# waterworx.net
KiCad netlist of a schematic drawn in EAGLE
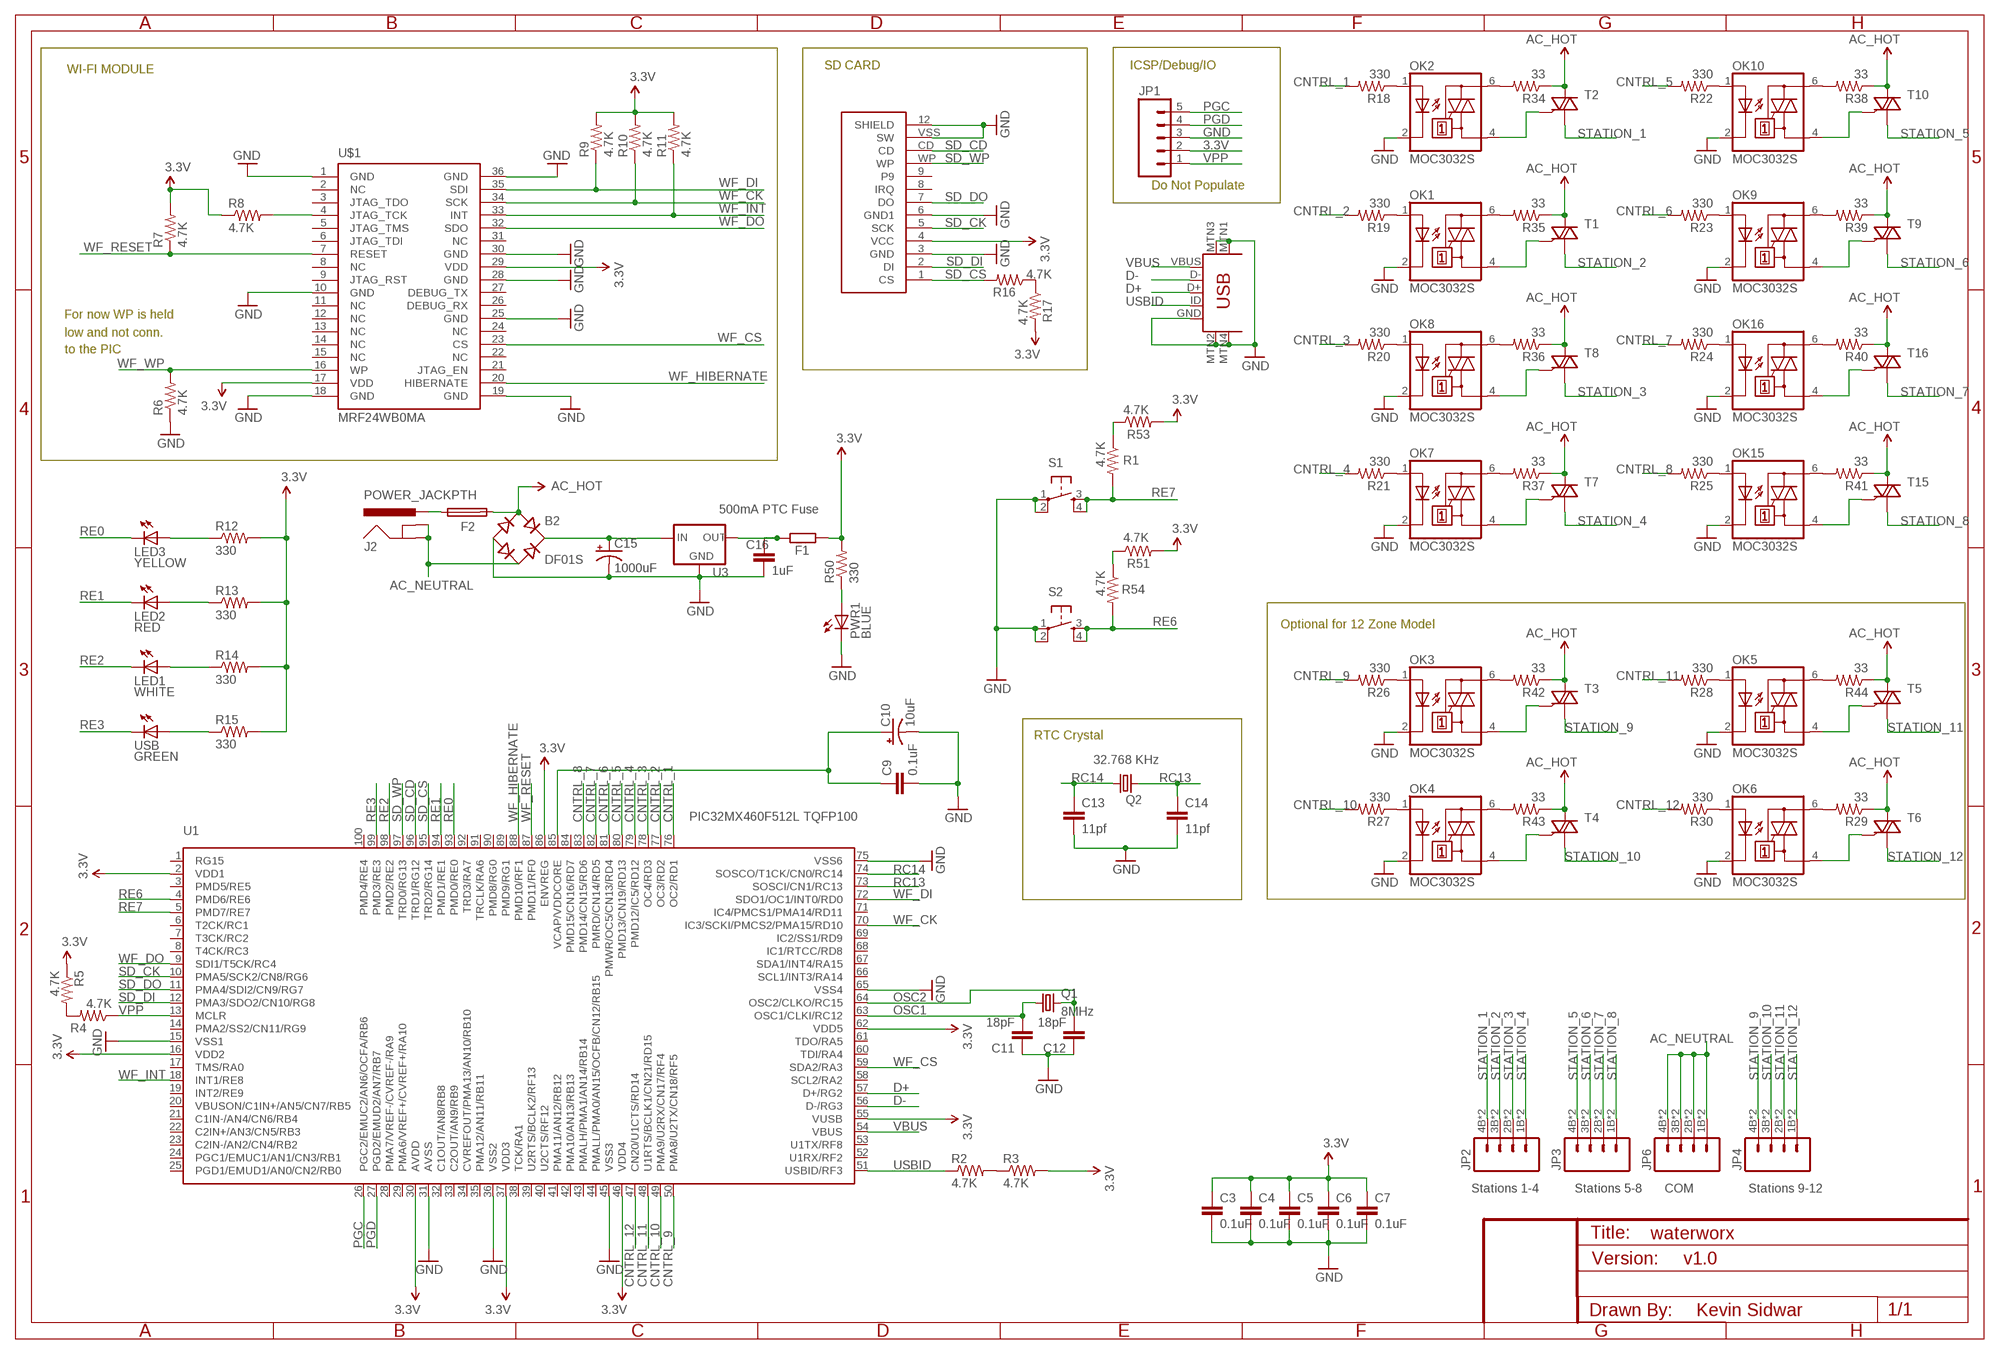
[diagram p0: schematic, sheet 1]

(export (version "E")
  (design (tool "Eeschema 10.0.6"))
  (components
    (comp (ref "B2")
      (value "DF01S")
      (footprint "eagle-import:DFS")
      (libsource (lib "eagle-import") (part "DFS01"))
    )
    (comp (ref "C3")
      (value "0.1uF")
      (footprint "eagle-import:0603")
      (libsource (lib "eagle-import") (part "CAP0603"))
    )
    (comp (ref "C4")
      (value "0.1uF")
      (footprint "eagle-import:0603")
      (libsource (lib "eagle-import") (part "CAP0603"))
    )
    (comp (ref "C5")
      (value "0.1uF")
      (footprint "eagle-import:0603")
      (libsource (lib "eagle-import") (part "CAP0603"))
    )
    (comp (ref "C6")
      (value "0.1uF")
      (footprint "eagle-import:0603")
      (libsource (lib "eagle-import") (part "CAP0603"))
    )
    (comp (ref "C7")
      (value "0.1uF")
      (footprint "eagle-import:0603")
      (libsource (lib "eagle-import") (part "SparkFun02-20-08_CAP0603"))
    )
    (comp (ref "C9")
      (value "0.1uF")
      (footprint "eagle-import:0603")
      (libsource (lib "eagle-import") (part "CAP0603"))
    )
    (comp (ref "C10")
      (value "10uF")
      (footprint "eagle-import:EIA3528")
      (libsource (lib "eagle-import") (part "CAP_POL3528"))
    )
    (comp (ref "C11")
      (value "18pF")
      (footprint "eagle-import:0603")
      (libsource (lib "eagle-import") (part "CAP0603"))
    )
    (comp (ref "C12")
      (value "18pF")
      (footprint "eagle-import:0603")
      (libsource (lib "eagle-import") (part "CAP0603"))
    )
    (comp (ref "C13")
      (value "11pf")
      (footprint "eagle-import:0603")
      (libsource (lib "eagle-import") (part "CAP0603"))
    )
    (comp (ref "C14")
      (value "11pf")
      (footprint "eagle-import:0603")
      (libsource (lib "eagle-import") (part "CAP0603"))
    )
    (comp (ref "C15")
      (value "1000uF")
      (footprint "eagle-import:E7,5-18")
      (libsource (lib "eagle-import") (part "CPOL-USE7.5-18"))
    )
    (comp (ref "C16")
      (value "1uF")
      (footprint "eagle-import:0603-CAP")
      (libsource (lib "eagle-import") (part "CAP0603-CAP"))
    )
    (comp (ref "F1")
      (value "500mA PTC Fuse")
      (footprint "eagle-import:M1206")
      (libsource (lib "eagle-import") (part "R-EU_M1206"))
    )
    (comp (ref "F2")
      (value "LITTLEFUSENANO")
      (footprint "eagle-import:NANO2_HOLDER")
      (libsource (lib "eagle-import") (part "LITTLEFUSENANO"))
    )
    (comp (ref "J2")
      (value "POWER_JACKPTH")
      (footprint "eagle-import:POWER_JACK_PTH")
      (libsource (lib "eagle-import") (part "POWER_JACKPTH"))
    )
    (comp (ref "JP1")
      (value "M05LOCK")
      (footprint "eagle-import:1X05_LOCK")
      (libsource (lib "eagle-import") (part "M05LOCK"))
    )
    (comp (ref "JP2")
      (value "Stations 1-4")
      (footprint "eagle-import:PHOENIX_TERMINAL_4")
      (libsource (lib "eagle-import") (part "M04PHX"))
    )
    (comp (ref "JP3")
      (value "Stations 5-8")
      (footprint "eagle-import:PHOENIX_TERMINAL_4")
      (libsource (lib "eagle-import") (part "M04PHX"))
    )
    (comp (ref "JP4")
      (value "Stations 9-12")
      (footprint "eagle-import:PHOENIX_TERMINAL_4")
      (libsource (lib "eagle-import") (part "M04PHX"))
    )
    (comp (ref "JP6")
      (value "COM")
      (footprint "eagle-import:PHOENIX_TERMINAL_4")
      (libsource (lib "eagle-import") (part "M04PHX"))
    )
    (comp (ref "LED1")
      (value "WHITE")
      (footprint "eagle-import:LED-0603")
      (libsource (lib "eagle-import") (part "LED0603"))
    )
    (comp (ref "LED2")
      (value "RED")
      (footprint "eagle-import:LED-0603")
      (libsource (lib "eagle-import") (part "LED0603"))
    )
    (comp (ref "LED3")
      (value "YELLOW")
      (footprint "eagle-import:LED-0603")
      (libsource (lib "eagle-import") (part "LED0603"))
    )
    (comp (ref "OK1")
      (value "MOC3032S")
      (footprint "eagle-import:DIL6-SMD")
      (fields (field (name "MF") "FAIRCHILD SEMICONDUCTOR") (field (name "MPN") "MOC3032S-M"))
      (libsource (lib "eagle-import") (part "MOC30S32"))
    )
    (comp (ref "OK2")
      (value "MOC3032S")
      (footprint "eagle-import:DIL6-SMD")
      (fields (field (name "MF") "FAIRCHILD SEMICONDUCTOR") (field (name "MPN") "MOC3032S-M"))
      (libsource (lib "eagle-import") (part "MOC30S32"))
    )
    (comp (ref "OK3")
      (value "MOC3032S")
      (footprint "eagle-import:DIL6-SMD")
      (fields (field (name "MF") "FAIRCHILD SEMICONDUCTOR") (field (name "MPN") "MOC3032S-M"))
      (libsource (lib "eagle-import") (part "MOC30S32"))
    )
    (comp (ref "OK4")
      (value "MOC3032S")
      (footprint "eagle-import:DIL6-SMD")
      (fields (field (name "MF") "FAIRCHILD SEMICONDUCTOR") (field (name "MPN") "MOC3032S-M"))
      (libsource (lib "eagle-import") (part "MOC30S32"))
    )
    (comp (ref "OK5")
      (value "MOC3032S")
      (footprint "eagle-import:DIL6-SMD")
      (fields (field (name "MF") "FAIRCHILD SEMICONDUCTOR") (field (name "MPN") "MOC3032S-M"))
      (libsource (lib "eagle-import") (part "MOC30S32"))
    )
    (comp (ref "OK6")
      (value "MOC3032S")
      (footprint "eagle-import:DIL6-SMD")
      (fields (field (name "MF") "FAIRCHILD SEMICONDUCTOR") (field (name "MPN") "MOC3032S-M"))
      (libsource (lib "eagle-import") (part "MOC30S32"))
    )
    (comp (ref "OK7")
      (value "MOC3032S")
      (footprint "eagle-import:DIL6-SMD")
      (fields (field (name "MF") "FAIRCHILD SEMICONDUCTOR") (field (name "MPN") "MOC3032S-M"))
      (libsource (lib "eagle-import") (part "MOC30S32"))
    )
    (comp (ref "OK8")
      (value "MOC3032S")
      (footprint "eagle-import:DIL6-SMD")
      (fields (field (name "MF") "FAIRCHILD SEMICONDUCTOR") (field (name "MPN") "MOC3032S-M"))
      (libsource (lib "eagle-import") (part "MOC30S32"))
    )
    (comp (ref "OK9")
      (value "MOC3032S")
      (footprint "eagle-import:DIL6-SMD")
      (fields (field (name "MF") "FAIRCHILD SEMICONDUCTOR") (field (name "MPN") "MOC3032S-M"))
      (libsource (lib "eagle-import") (part "MOC30S32"))
    )
    (comp (ref "OK10")
      (value "MOC3032S")
      (footprint "eagle-import:DIL6-SMD")
      (fields (field (name "MF") "FAIRCHILD SEMICONDUCTOR") (field (name "MPN") "MOC3032S-M"))
      (libsource (lib "eagle-import") (part "MOC30S32"))
    )
    (comp (ref "OK15")
      (value "MOC3032S")
      (footprint "eagle-import:DIL6-SMD")
      (fields (field (name "MF") "FAIRCHILD SEMICONDUCTOR") (field (name "MPN") "MOC3032S-M"))
      (libsource (lib "eagle-import") (part "MOC30S32"))
    )
    (comp (ref "OK16")
      (value "MOC3032S")
      (footprint "eagle-import:DIL6-SMD")
      (fields (field (name "MF") "FAIRCHILD SEMICONDUCTOR") (field (name "MPN") "MOC3032S-M"))
      (libsource (lib "eagle-import") (part "MOC30S32"))
    )
    (comp (ref "PWR1")
      (value "BLUE")
      (footprint "eagle-import:LED-0603")
      (libsource (lib "eagle-import") (part "LED0603"))
    )
    (comp (ref "Q1")
      (value "8MHz")
      (footprint "eagle-import:CRYSTAL-SMD-5X3")
      (libsource (lib "eagle-import") (part "CRYSTAL5X3"))
    )
    (comp (ref "Q2")
      (value "32.768 KHz")
      (footprint "eagle-import:CRYSTAL-SMD-4X2")
      (libsource (lib "eagle-import") (part "CRYSTAL4X2"))
    )
    (comp (ref "R1")
      (value "4.7K")
      (footprint "eagle-import:0603")
      (libsource (lib "eagle-import") (part "RESISTOR0603"))
    )
    (comp (ref "R2")
      (value "4.7K")
      (footprint "eagle-import:0603-RES")
      (libsource (lib "eagle-import") (part "RESISTOR0603-RES"))
    )
    (comp (ref "R3")
      (value "4.7K")
      (footprint "eagle-import:0603-RES")
      (libsource (lib "eagle-import") (part "RESISTOR0603-RES"))
    )
    (comp (ref "R4")
      (value "4.7K")
      (footprint "eagle-import:0603-RES")
      (libsource (lib "eagle-import") (part "RESISTOR0603-RES"))
    )
    (comp (ref "R5")
      (value "4.7K")
      (footprint "eagle-import:0603-RES")
      (libsource (lib "eagle-import") (part "RESISTOR0603-RES"))
    )
    (comp (ref "R6")
      (value "4.7K")
      (footprint "eagle-import:0603-RES")
      (libsource (lib "eagle-import") (part "RESISTOR0603-RES"))
    )
    (comp (ref "R7")
      (value "4.7K")
      (footprint "eagle-import:0603-RES")
      (libsource (lib "eagle-import") (part "RESISTOR0603-RES"))
    )
    (comp (ref "R8")
      (value "4.7K")
      (footprint "eagle-import:0603-RES")
      (libsource (lib "eagle-import") (part "RESISTOR0603-RES"))
    )
    (comp (ref "R9")
      (value "4.7K")
      (footprint "eagle-import:0603-RES")
      (libsource (lib "eagle-import") (part "RESISTOR0603-RES"))
    )
    (comp (ref "R10")
      (value "4.7K")
      (footprint "eagle-import:0603-RES")
      (libsource (lib "eagle-import") (part "RESISTOR0603-RES"))
    )
    (comp (ref "R11")
      (value "4.7K")
      (footprint "eagle-import:0603-RES")
      (libsource (lib "eagle-import") (part "RESISTOR0603-RES"))
    )
    (comp (ref "R12")
      (value "330")
      (footprint "eagle-import:0603-RES")
      (libsource (lib "eagle-import") (part "RESISTOR0603-RES"))
    )
    (comp (ref "R13")
      (value "330")
      (footprint "eagle-import:0603-RES")
      (libsource (lib "eagle-import") (part "RESISTOR0603-RES"))
    )
    (comp (ref "R14")
      (value "330")
      (footprint "eagle-import:0603-RES")
      (libsource (lib "eagle-import") (part "RESISTOR0603-RES"))
    )
    (comp (ref "R15")
      (value "330")
      (footprint "eagle-import:0603-RES")
      (libsource (lib "eagle-import") (part "RESISTOR0603-RES"))
    )
    (comp (ref "R16")
      (value "4.7K")
      (footprint "eagle-import:0603-RES")
      (libsource (lib "eagle-import") (part "RESISTOR0603-RES"))
    )
    (comp (ref "R17")
      (value "4.7K")
      (footprint "eagle-import:0603-RES")
      (libsource (lib "eagle-import") (part "RESISTOR0603-RES"))
    )
    (comp (ref "R18")
      (value "330")
      (footprint "eagle-import:0603-RES")
      (libsource (lib "eagle-import") (part "RESISTOR0603-RES"))
    )
    (comp (ref "R19")
      (value "330")
      (footprint "eagle-import:0603-RES")
      (libsource (lib "eagle-import") (part "RESISTOR0603-RES"))
    )
    (comp (ref "R20")
      (value "330")
      (footprint "eagle-import:0603-RES")
      (libsource (lib "eagle-import") (part "RESISTOR0603-RES"))
    )
    (comp (ref "R21")
      (value "330")
      (footprint "eagle-import:0603-RES")
      (libsource (lib "eagle-import") (part "RESISTOR0603-RES"))
    )
    (comp (ref "R22")
      (value "330")
      (footprint "eagle-import:0603-RES")
      (libsource (lib "eagle-import") (part "RESISTOR0603-RES"))
    )
    (comp (ref "R23")
      (value "330")
      (footprint "eagle-import:0603-RES")
      (libsource (lib "eagle-import") (part "RESISTOR0603-RES"))
    )
    (comp (ref "R24")
      (value "330")
      (footprint "eagle-import:0603-RES")
      (libsource (lib "eagle-import") (part "RESISTOR0603-RES"))
    )
    (comp (ref "R25")
      (value "330")
      (footprint "eagle-import:0603-RES")
      (libsource (lib "eagle-import") (part "RESISTOR0603-RES"))
    )
    (comp (ref "R26")
      (value "330")
      (footprint "eagle-import:0603-RES")
      (libsource (lib "eagle-import") (part "RESISTOR0603-RES"))
    )
    (comp (ref "R27")
      (value "330")
      (footprint "eagle-import:0603-RES")
      (libsource (lib "eagle-import") (part "RESISTOR0603-RES"))
    )
    (comp (ref "R28")
      (value "330")
      (footprint "eagle-import:0603-RES")
      (libsource (lib "eagle-import") (part "RESISTOR0603-RES"))
    )
    (comp (ref "R29")
      (value "33")
      (footprint "eagle-import:0603-RES")
      (libsource (lib "eagle-import") (part "RESISTOR0603-RES"))
    )
    (comp (ref "R30")
      (value "330")
      (footprint "eagle-import:0603-RES")
      (libsource (lib "eagle-import") (part "RESISTOR0603-RES"))
    )
    (comp (ref "R34")
      (value "33")
      (footprint "eagle-import:0603-RES")
      (libsource (lib "eagle-import") (part "RESISTOR0603-RES"))
    )
    (comp (ref "R35")
      (value "33")
      (footprint "eagle-import:0603-RES")
      (libsource (lib "eagle-import") (part "RESISTOR0603-RES"))
    )
    (comp (ref "R36")
      (value "33")
      (footprint "eagle-import:0603-RES")
      (libsource (lib "eagle-import") (part "RESISTOR0603-RES"))
    )
    (comp (ref "R37")
      (value "33")
      (footprint "eagle-import:0603-RES")
      (libsource (lib "eagle-import") (part "RESISTOR0603-RES"))
    )
    (comp (ref "R38")
      (value "33")
      (footprint "eagle-import:0603-RES")
      (libsource (lib "eagle-import") (part "RESISTOR0603-RES"))
    )
    (comp (ref "R39")
      (value "33")
      (footprint "eagle-import:0603-RES")
      (libsource (lib "eagle-import") (part "RESISTOR0603-RES"))
    )
    (comp (ref "R40")
      (value "33")
      (footprint "eagle-import:0603-RES")
      (libsource (lib "eagle-import") (part "RESISTOR0603-RES"))
    )
    (comp (ref "R41")
      (value "33")
      (footprint "eagle-import:0603-RES")
      (libsource (lib "eagle-import") (part "RESISTOR0603-RES"))
    )
    (comp (ref "R42")
      (value "33")
      (footprint "eagle-import:0603-RES")
      (libsource (lib "eagle-import") (part "RESISTOR0603-RES"))
    )
    (comp (ref "R43")
      (value "33")
      (footprint "eagle-import:0603-RES")
      (libsource (lib "eagle-import") (part "RESISTOR0603-RES"))
    )
    (comp (ref "R44")
      (value "33")
      (footprint "eagle-import:0603-RES")
      (libsource (lib "eagle-import") (part "RESISTOR0603-RES"))
    )
    (comp (ref "R50")
      (value "330")
      (footprint "eagle-import:0603-RES")
      (libsource (lib "eagle-import") (part "RESISTOR0603-RES"))
    )
    (comp (ref "R51")
      (value "4.7K")
      (footprint "eagle-import:0603")
      (libsource (lib "eagle-import") (part "RESISTOR0603"))
    )
    (comp (ref "R53")
      (value "4.7K")
      (footprint "eagle-import:0603")
      (libsource (lib "eagle-import") (part "RESISTOR0603"))
    )
    (comp (ref "R54")
      (value "4.7K")
      (footprint "eagle-import:0603")
      (libsource (lib "eagle-import") (part "RESISTOR0603"))
    )
    (comp (ref "S1")
      (value "TAC_SWITCHB3FS")
      (footprint "eagle-import:SWITCH-OMRON")
      (libsource (lib "eagle-import") (part "TAC_SWITCHB3FS"))
    )
    (comp (ref "S2")
      (value "TAC_SWITCHB3FS")
      (footprint "eagle-import:SWITCH-OMRON")
      (libsource (lib "eagle-import") (part "TAC_SWITCHB3FS"))
    )
    (comp (ref "T1")
      (value "LF-TRIACSOT223")
      (footprint "eagle-import:SOT223")
      (libsource (lib "eagle-import") (part "LF-TRIACSOT223"))
    )
    (comp (ref "T2")
      (value "LF-TRIACSOT223")
      (footprint "eagle-import:SOT223")
      (libsource (lib "eagle-import") (part "LF-TRIACSOT223"))
    )
    (comp (ref "T3")
      (value "LF-TRIACSOT223")
      (footprint "eagle-import:SOT223")
      (libsource (lib "eagle-import") (part "LF-TRIACSOT223"))
    )
    (comp (ref "T4")
      (value "LF-TRIACSOT223")
      (footprint "eagle-import:SOT223")
      (libsource (lib "eagle-import") (part "LF-TRIACSOT223"))
    )
    (comp (ref "T5")
      (value "LF-TRIACSOT223")
      (footprint "eagle-import:SOT223")
      (libsource (lib "eagle-import") (part "LF-TRIACSOT223"))
    )
    (comp (ref "T6")
      (value "LF-TRIACSOT223")
      (footprint "eagle-import:SOT223")
      (libsource (lib "eagle-import") (part "LF-TRIACSOT223"))
    )
    (comp (ref "T7")
      (value "LF-TRIACSOT223")
      (footprint "eagle-import:SOT223")
      (libsource (lib "eagle-import") (part "LF-TRIACSOT223"))
    )
    (comp (ref "T8")
      (value "LF-TRIACSOT223")
      (footprint "eagle-import:SOT223")
      (libsource (lib "eagle-import") (part "LF-TRIACSOT223"))
    )
    (comp (ref "T9")
      (value "LF-TRIACSOT223")
      (footprint "eagle-import:SOT223")
      (libsource (lib "eagle-import") (part "LF-TRIACSOT223"))
    )
    (comp (ref "T10")
      (value "LF-TRIACSOT223")
      (footprint "eagle-import:SOT223")
      (libsource (lib "eagle-import") (part "LF-TRIACSOT223"))
    )
    (comp (ref "T15")
      (value "LF-TRIACSOT223")
      (footprint "eagle-import:SOT223")
      (libsource (lib "eagle-import") (part "LF-TRIACSOT223"))
    )
    (comp (ref "T16")
      (value "LF-TRIACSOT223")
      (footprint "eagle-import:SOT223")
      (libsource (lib "eagle-import") (part "LF-TRIACSOT223"))
    )
    (comp (ref "U$1")
      (value "MRF24WB0MA")
      (footprint "eagle-import:SMD_MRF")
      (libsource (lib "eagle-import") (part "MRF24WB0MA"))
    )
    (comp (ref "U$2")
      (value "SD_CARD_SOCKETALPS")
      (footprint "eagle-import:SD_ALPS")
      (libsource (lib "eagle-import") (part "SD_CARD_SOCKETALPS"))
    )
    (comp (ref "U$21")
      (value "USB-MINIB-5PIN")
      (footprint "eagle-import:USB-MINIB")
      (libsource (lib "eagle-import") (part "USB-MINIB-5PIN"))
    )
    (comp (ref "U1")
      (value "PIC32MX460F512L TQFP100")
      (footprint "eagle-import:TQFP100")
      (libsource (lib "eagle-import") (part "PIC32MX4XXLTQFP100"))
    )
    (comp (ref "U3")
      (value "RECOM_X.X_REG78XX")
      (footprint "eagle-import:RECOM")
      (libsource (lib "eagle-import") (part "RECOM_X.X_REG78XX"))
    )
    (comp (ref "USB")
      (value "GREEN")
      (footprint "eagle-import:LED-0603")
      (libsource (lib "eagle-import") (part "LED0603"))
    )
  )
  (nets
    (net (code "1") (name "/AC_NEUTRAL") (class "Default")
      (node (ref "B2") (pin "AC2") (pinfunction "AC2_AC2") (pintype "passive"))
      (node (ref "J2") (pin "GND") (pinfunction "GND_GND") (pintype "bidirectional"))
      (node (ref "J2") (pin "GNDBREAK") (pinfunction "GNDBREAK_GNDBREAK") (pintype "bidirectional"))
      (node (ref "JP6") (pin "1B") (pinfunction "1_1B") (pintype "passive"))
      (node (ref "JP6") (pin "1T") (pinfunction "1_1T") (pintype "passive"))
      (node (ref "JP6") (pin "2B") (pinfunction "2_2B") (pintype "passive"))
      (node (ref "JP6") (pin "2T") (pinfunction "2_2T") (pintype "passive"))
      (node (ref "JP6") (pin "3B") (pinfunction "3_3B") (pintype "passive"))
      (node (ref "JP6") (pin "3T") (pinfunction "3_3T") (pintype "passive"))
      (node (ref "JP6") (pin "4B") (pinfunction "4_4B") (pintype "passive"))
      (node (ref "JP6") (pin "4T") (pinfunction "4_4T") (pintype "passive"))
    )
    (net (code "2") (name "/CNTRL_1") (class "Default")
      (node (ref "R18") (pin "2") (pinfunction "2_2") (pintype "passive"))
      (node (ref "U1") (pin "76") (pinfunction "OC2/RD1_76") (pintype "bidirectional"))
    )
    (net (code "3") (name "/CNTRL_2") (class "Default")
      (node (ref "R19") (pin "2") (pinfunction "2_2") (pintype "passive"))
      (node (ref "U1") (pin "77") (pinfunction "OC3/RD2_77") (pintype "bidirectional"))
    )
    (net (code "4") (name "/CNTRL_3") (class "Default")
      (node (ref "R20") (pin "2") (pinfunction "2_2") (pintype "passive"))
      (node (ref "U1") (pin "78") (pinfunction "OC4/RD3_78") (pintype "bidirectional"))
    )
    (net (code "5") (name "/CNTRL_4") (class "Default")
      (node (ref "R21") (pin "2") (pinfunction "2_2") (pintype "passive"))
      (node (ref "U1") (pin "79") (pinfunction "PMD12/IC5/RD12_79") (pintype "bidirectional"))
    )
    (net (code "6") (name "/CNTRL_5") (class "Default")
      (node (ref "R22") (pin "2") (pinfunction "2_2") (pintype "passive"))
      (node (ref "U1") (pin "80") (pinfunction "PMD13/CN19/RD13_80") (pintype "bidirectional"))
    )
    (net (code "7") (name "/CNTRL_6") (class "Default")
      (node (ref "R23") (pin "2") (pinfunction "2_2") (pintype "passive"))
      (node (ref "U1") (pin "81") (pinfunction "PMWR/OC5/CN13/RD4_81") (pintype "bidirectional"))
    )
    (net (code "8") (name "/CNTRL_7") (class "Default")
      (node (ref "R24") (pin "2") (pinfunction "2_2") (pintype "passive"))
      (node (ref "U1") (pin "82") (pinfunction "PMRD/CN14/RD5_82") (pintype "bidirectional"))
    )
    (net (code "9") (name "/CNTRL_8") (class "Default")
      (node (ref "R25") (pin "2") (pinfunction "2_2") (pintype "passive"))
      (node (ref "U1") (pin "83") (pinfunction "PMD14/CN15/RD6_83") (pintype "bidirectional"))
    )
    (net (code "10") (name "/CNTRL_9") (class "Default")
      (node (ref "R26") (pin "2") (pinfunction "2_2") (pintype "passive"))
      (node (ref "U1") (pin "50") (pinfunction "PMA8/U2TX/CN18/RF5_50") (pintype "bidirectional"))
    )
    (net (code "11") (name "/CNTRL_10") (class "Default")
      (node (ref "R27") (pin "2") (pinfunction "2_2") (pintype "passive"))
      (node (ref "U1") (pin "49") (pinfunction "PMA9/U2RX/CN17/RF4_49") (pintype "bidirectional"))
    )
    (net (code "12") (name "/CNTRL_11") (class "Default")
      (node (ref "R28") (pin "2") (pinfunction "2_2") (pintype "passive"))
      (node (ref "U1") (pin "48") (pinfunction "U1RTS/BCLK1/CN21/RD15_48") (pintype "bidirectional"))
    )
    (net (code "13") (name "/CNTRL_12") (class "Default")
      (node (ref "R30") (pin "2") (pinfunction "2_2") (pintype "passive"))
      (node (ref "U1") (pin "47") (pinfunction "CN20/U1CTS/RD14_47") (pintype "bidirectional"))
    )
    (net (code "14") (name "/D+") (class "Default")
      (node (ref "U$21") (pin "D+") (pinfunction "D+_D+") (pintype "bidirectional"))
      (node (ref "U1") (pin "57") (pinfunction "D+/RG2_57") (pintype "bidirectional"))
    )
    (net (code "15") (name "/D-") (class "Default")
      (node (ref "U$21") (pin "D-") (pinfunction "D-_D-") (pintype "bidirectional"))
      (node (ref "U1") (pin "56") (pinfunction "D-/RG3_56") (pintype "bidirectional"))
    )
    (net (code "16") (name "/OSC1") (class "Default")
      (node (ref "C11") (pin "2") (pinfunction "2_2") (pintype "passive"))
      (node (ref "Q1") (pin "1") (pinfunction "1_1") (pintype "passive"))
      (node (ref "U1") (pin "63") (pinfunction "OSC1/CLKI/RC12_63") (pintype "bidirectional"))
    )
    (net (code "17") (name "/OSC2") (class "Default")
      (node (ref "C12") (pin "2") (pinfunction "2_2") (pintype "passive"))
      (node (ref "Q1") (pin "3") (pinfunction "2_3") (pintype "passive"))
      (node (ref "U1") (pin "64") (pinfunction "OSC2/CLKO/RC15_64") (pintype "bidirectional"))
    )
    (net (code "18") (name "/PGC") (class "Default")
      (node (ref "JP1") (pin "5") (pinfunction "5_5") (pintype "passive"))
      (node (ref "U1") (pin "26") (pinfunction "PGC2/EMUC2/AN6/OCFA/RB6_26") (pintype "bidirectional"))
    )
    (net (code "19") (name "/PGD") (class "Default")
      (node (ref "JP1") (pin "4") (pinfunction "4_4") (pintype "passive"))
      (node (ref "U1") (pin "27") (pinfunction "PGD2/EMUD2/AN7/RB7_27") (pintype "bidirectional"))
    )
    (net (code "20") (name "/RC13") (class "Default")
      (node (ref "C14") (pin "1") (pinfunction "1_1") (pintype "passive"))
      (node (ref "Q2") (pin "P$2") (pinfunction "2_P$2") (pintype "passive"))
      (node (ref "U1") (pin "73") (pinfunction "SOSCI/CN1/RC13_73") (pintype "bidirectional"))
    )
    (net (code "21") (name "/RC14") (class "Default")
      (node (ref "C13") (pin "1") (pinfunction "1_1") (pintype "passive"))
      (node (ref "Q2") (pin "P$1") (pinfunction "1_P$1") (pintype "passive"))
      (node (ref "U1") (pin "74") (pinfunction "SOSCO/T1CK/CN0/RC14_74") (pintype "bidirectional"))
    )
    (net (code "22") (name "/RE0") (class "Default")
      (node (ref "LED3") (pin "C") (pinfunction "C_C") (pintype "passive"))
      (node (ref "U1") (pin "93") (pinfunction "PMD0/RE0_93") (pintype "bidirectional"))
    )
    (net (code "23") (name "/RE1") (class "Default")
      (node (ref "LED2") (pin "C") (pinfunction "C_C") (pintype "passive"))
      (node (ref "U1") (pin "94") (pinfunction "PMD1/RE1_94") (pintype "bidirectional"))
    )
    (net (code "24") (name "/RE2") (class "Default")
      (node (ref "LED1") (pin "C") (pinfunction "C_C") (pintype "passive"))
      (node (ref "U1") (pin "98") (pinfunction "PMD2/RE2_98") (pintype "bidirectional"))
    )
    (net (code "25") (name "/RE3") (class "Default")
      (node (ref "U1") (pin "99") (pinfunction "PMD3/RE3_99") (pintype "bidirectional"))
      (node (ref "USB") (pin "C") (pinfunction "C_C") (pintype "passive"))
    )
    (net (code "26") (name "/RE6") (class "Default")
      (node (ref "R54") (pin "2") (pinfunction "2_2") (pintype "passive"))
      (node (ref "S2") (pin "3") (pinfunction "3_3") (pintype "passive"))
      (node (ref "S2") (pin "4") (pinfunction "4_4") (pintype "passive"))
      (node (ref "U1") (pin "4") (pinfunction "PMD6/RE6_4") (pintype "bidirectional"))
    )
    (net (code "27") (name "/RE7") (class "Default")
      (node (ref "R1") (pin "2") (pinfunction "2_2") (pintype "passive"))
      (node (ref "S1") (pin "3") (pinfunction "3_3") (pintype "passive"))
      (node (ref "S1") (pin "4") (pinfunction "4_4") (pintype "passive"))
      (node (ref "U1") (pin "5") (pinfunction "PMD7/RE7_5") (pintype "bidirectional"))
    )
    (net (code "28") (name "/SD_CD") (class "Default")
      (node (ref "U$2") (pin "CD") (pinfunction "CD_CD") (pintype "bidirectional"))
      (node (ref "U1") (pin "96") (pinfunction "TRD1/RG12_96") (pintype "bidirectional"))
    )
    (net (code "29") (name "/SD_CK") (class "Default")
      (node (ref "U$2") (pin "5") (pinfunction "SCK_5") (pintype "bidirectional"))
      (node (ref "U1") (pin "10") (pinfunction "PMA5/SCK2/CN8/RG6_10") (pintype "bidirectional"))
    )
    (net (code "30") (name "/SD_CS") (class "Default")
      (node (ref "R16") (pin "2") (pinfunction "2_2") (pintype "passive"))
      (node (ref "U$2") (pin "1") (pinfunction "CS_1") (pintype "bidirectional"))
      (node (ref "U1") (pin "95") (pinfunction "TRD2/RG14_95") (pintype "bidirectional"))
    )
    (net (code "31") (name "/SD_DI") (class "Default")
      (node (ref "U$2") (pin "2") (pinfunction "DI_2") (pintype "bidirectional"))
      (node (ref "U1") (pin "12") (pinfunction "PMA3/SDO2/CN10/RG8_12") (pintype "bidirectional"))
    )
    (net (code "32") (name "/SD_DO") (class "Default")
      (node (ref "U$2") (pin "7") (pinfunction "DO_7") (pintype "bidirectional"))
      (node (ref "U1") (pin "11") (pinfunction "PMA4/SDI2/CN9/RG7_11") (pintype "bidirectional"))
    )
    (net (code "33") (name "/SD_WP") (class "Default")
      (node (ref "U$2") (pin "WP") (pinfunction "WP_WP") (pintype "bidirectional"))
      (node (ref "U1") (pin "97") (pinfunction "TRD0/RG13_97") (pintype "bidirectional"))
    )
    (net (code "34") (name "/STATION_1") (class "Default")
      (node (ref "JP2") (pin "4B") (pinfunction "4_4B") (pintype "passive"))
      (node (ref "JP2") (pin "4T") (pinfunction "4_4T") (pintype "passive"))
      (node (ref "T2") (pin "1") (pinfunction "A1_1") (pintype "passive"))
    )
    (net (code "35") (name "/STATION_2") (class "Default")
      (node (ref "JP2") (pin "3B") (pinfunction "3_3B") (pintype "passive"))
      (node (ref "JP2") (pin "3T") (pinfunction "3_3T") (pintype "passive"))
      (node (ref "T1") (pin "1") (pinfunction "A1_1") (pintype "passive"))
    )
    (net (code "36") (name "/STATION_3") (class "Default")
      (node (ref "JP2") (pin "2B") (pinfunction "2_2B") (pintype "passive"))
      (node (ref "JP2") (pin "2T") (pinfunction "2_2T") (pintype "passive"))
      (node (ref "T8") (pin "1") (pinfunction "A1_1") (pintype "passive"))
    )
    (net (code "37") (name "/STATION_4") (class "Default")
      (node (ref "JP2") (pin "1B") (pinfunction "1_1B") (pintype "passive"))
      (node (ref "JP2") (pin "1T") (pinfunction "1_1T") (pintype "passive"))
      (node (ref "T7") (pin "1") (pinfunction "A1_1") (pintype "passive"))
    )
    (net (code "38") (name "/STATION_5") (class "Default")
      (node (ref "JP3") (pin "4B") (pinfunction "4_4B") (pintype "passive"))
      (node (ref "JP3") (pin "4T") (pinfunction "4_4T") (pintype "passive"))
      (node (ref "T10") (pin "1") (pinfunction "A1_1") (pintype "passive"))
    )
    (net (code "39") (name "/STATION_6") (class "Default")
      (node (ref "JP3") (pin "3B") (pinfunction "3_3B") (pintype "passive"))
      (node (ref "JP3") (pin "3T") (pinfunction "3_3T") (pintype "passive"))
      (node (ref "T9") (pin "1") (pinfunction "A1_1") (pintype "passive"))
    )
    (net (code "40") (name "/STATION_7") (class "Default")
      (node (ref "JP3") (pin "2B") (pinfunction "2_2B") (pintype "passive"))
      (node (ref "JP3") (pin "2T") (pinfunction "2_2T") (pintype "passive"))
      (node (ref "T16") (pin "1") (pinfunction "A1_1") (pintype "passive"))
    )
    (net (code "41") (name "/STATION_8") (class "Default")
      (node (ref "JP3") (pin "1B") (pinfunction "1_1B") (pintype "passive"))
      (node (ref "JP3") (pin "1T") (pinfunction "1_1T") (pintype "passive"))
      (node (ref "T15") (pin "1") (pinfunction "A1_1") (pintype "passive"))
    )
    (net (code "42") (name "/STATION_9") (class "Default")
      (node (ref "JP4") (pin "4B") (pinfunction "4_4B") (pintype "passive"))
      (node (ref "JP4") (pin "4T") (pinfunction "4_4T") (pintype "passive"))
      (node (ref "T3") (pin "1") (pinfunction "A1_1") (pintype "passive"))
    )
    (net (code "43") (name "/STATION_10") (class "Default")
      (node (ref "JP4") (pin "3B") (pinfunction "3_3B") (pintype "passive"))
      (node (ref "JP4") (pin "3T") (pinfunction "3_3T") (pintype "passive"))
      (node (ref "T4") (pin "1") (pinfunction "A1_1") (pintype "passive"))
    )
    (net (code "44") (name "/STATION_11") (class "Default")
      (node (ref "JP4") (pin "2B") (pinfunction "2_2B") (pintype "passive"))
      (node (ref "JP4") (pin "2T") (pinfunction "2_2T") (pintype "passive"))
      (node (ref "T5") (pin "1") (pinfunction "A1_1") (pintype "passive"))
    )
    (net (code "45") (name "/STATION_12") (class "Default")
      (node (ref "JP4") (pin "1B") (pinfunction "1_1B") (pintype "passive"))
      (node (ref "JP4") (pin "1T") (pinfunction "1_1T") (pintype "passive"))
      (node (ref "T6") (pin "1") (pinfunction "A1_1") (pintype "passive"))
    )
    (net (code "46") (name "/USBID") (class "Default")
      (node (ref "R2") (pin "1") (pinfunction "1_1") (pintype "passive"))
      (node (ref "U$21") (pin "ID") (pinfunction "ID_ID") (pintype "bidirectional"))
      (node (ref "U1") (pin "51") (pinfunction "USBID/RF3_51") (pintype "bidirectional"))
    )
    (net (code "47") (name "/VBUS") (class "Default")
      (node (ref "U$21") (pin "VBUS") (pinfunction "VBUS_VBUS") (pintype "bidirectional"))
      (node (ref "U1") (pin "54") (pinfunction "VBUS_54") (pintype "bidirectional"))
    )
    (net (code "48") (name "/VPP") (class "Default")
      (node (ref "JP1") (pin "1") (pinfunction "1_1") (pintype "passive"))
      (node (ref "R4") (pin "1") (pinfunction "1_1") (pintype "passive"))
      (node (ref "U1") (pin "13") (pinfunction "MCLR_13") (pintype "bidirectional"))
    )
    (net (code "49") (name "/WF_CK") (class "Default")
      (node (ref "R10") (pin "1") (pinfunction "1_1") (pintype "passive"))
      (node (ref "U$1") (pin "34") (pinfunction "SCK_34") (pintype "bidirectional"))
      (node (ref "U1") (pin "70") (pinfunction "IC3/SCKI/PMCS2/PMA15/RD10_70") (pintype "bidirectional"))
    )
    (net (code "50") (name "/WF_CS") (class "Default")
      (node (ref "U$1") (pin "23") (pinfunction "CS_23") (pintype "bidirectional"))
      (node (ref "U1") (pin "59") (pinfunction "SDA2/RA3_59") (pintype "bidirectional"))
    )
    (net (code "51") (name "/WF_DI") (class "Default")
      (node (ref "R9") (pin "1") (pinfunction "1_1") (pintype "passive"))
      (node (ref "U$1") (pin "35") (pinfunction "SDI_35") (pintype "bidirectional"))
      (node (ref "U1") (pin "72") (pinfunction "SDO1/OC1/INT0/RD0_72") (pintype "bidirectional"))
    )
    (net (code "52") (name "/WF_DO") (class "Default")
      (node (ref "U$1") (pin "32") (pinfunction "SDO_32") (pintype "bidirectional"))
      (node (ref "U1") (pin "9") (pinfunction "SDI1/T5CK/RC4_9") (pintype "bidirectional"))
    )
    (net (code "53") (name "/WF_HIBERNATE") (class "Default")
      (node (ref "U$1") (pin "20") (pinfunction "HIBERNATE_20") (pintype "bidirectional"))
      (node (ref "U1") (pin "88") (pinfunction "PMD10/RF1_88") (pintype "bidirectional"))
    )
    (net (code "54") (name "/WF_INT") (class "Default")
      (node (ref "R11") (pin "1") (pinfunction "1_1") (pintype "passive"))
      (node (ref "U$1") (pin "33") (pinfunction "INT_33") (pintype "bidirectional"))
      (node (ref "U1") (pin "18") (pinfunction "INT1/RE8_18") (pintype "bidirectional"))
    )
    (net (code "55") (name "/WF_RESET") (class "Default")
      (node (ref "R7") (pin "1") (pinfunction "1_1") (pintype "passive"))
      (node (ref "U$1") (pin "7") (pinfunction "RESET_7") (pintype "bidirectional"))
      (node (ref "U1") (pin "87") (pinfunction "PMD11/RF0_87") (pintype "bidirectional"))
    )
    (net (code "56") (name "/WF_WP") (class "Default")
      (node (ref "R6") (pin "2") (pinfunction "2_2") (pintype "passive"))
      (node (ref "U$1") (pin "16") (pinfunction "WP_16") (pintype "bidirectional"))
    )
    (net (code "57") (name "3.3V") (class "Default")
      (node (ref "C3") (pin "1") (pinfunction "1_1") (pintype "passive"))
      (node (ref "C4") (pin "1") (pinfunction "1_1") (pintype "passive"))
      (node (ref "C5") (pin "1") (pinfunction "1_1") (pintype "passive"))
      (node (ref "C6") (pin "1") (pinfunction "1_1") (pintype "passive"))
      (node (ref "C7") (pin "1") (pinfunction "1_1") (pintype "passive"))
      (node (ref "F1") (pin "1") (pinfunction "1_1") (pintype "passive"))
      (node (ref "JP1") (pin "2") (pinfunction "2_2") (pintype "passive"))
      (node (ref "R10") (pin "2") (pinfunction "2_2") (pintype "passive"))
      (node (ref "R11") (pin "2") (pinfunction "2_2") (pintype "passive"))
      (node (ref "R12") (pin "2") (pinfunction "2_2") (pintype "passive"))
      (node (ref "R13") (pin "2") (pinfunction "2_2") (pintype "passive"))
      (node (ref "R14") (pin "2") (pinfunction "2_2") (pintype "passive"))
      (node (ref "R15") (pin "2") (pinfunction "2_2") (pintype "passive"))
      (node (ref "R17") (pin "2") (pinfunction "2_2") (pintype "passive"))
      (node (ref "R3") (pin "2") (pinfunction "2_2") (pintype "passive"))
      (node (ref "R5") (pin "1") (pinfunction "1_1") (pintype "passive"))
      (node (ref "R50") (pin "2") (pinfunction "2_2") (pintype "passive"))
      (node (ref "R51") (pin "2") (pinfunction "2_2") (pintype "passive"))
      (node (ref "R53") (pin "2") (pinfunction "2_2") (pintype "passive"))
      (node (ref "R7") (pin "2") (pinfunction "2_2") (pintype "passive"))
      (node (ref "R8") (pin "1") (pinfunction "1_1") (pintype "passive"))
      (node (ref "R9") (pin "2") (pinfunction "2_2") (pintype "passive"))
      (node (ref "U$1") (pin "17") (pinfunction "VDD_17") (pintype "bidirectional"))
      (node (ref "U$1") (pin "29") (pinfunction "VDD_29") (pintype "bidirectional"))
      (node (ref "U$2") (pin "4") (pinfunction "VCC_4") (pintype "bidirectional"))
      (node (ref "U1") (pin "16") (pinfunction "VDD2_16") (pintype "bidirectional"))
      (node (ref "U1") (pin "2") (pinfunction "VDD1_2") (pintype "bidirectional"))
      (node (ref "U1") (pin "30") (pinfunction "AVDD_30") (pintype "bidirectional"))
      (node (ref "U1") (pin "37") (pinfunction "VDD3_37") (pintype "bidirectional"))
      (node (ref "U1") (pin "46") (pinfunction "VDD4_46") (pintype "bidirectional"))
      (node (ref "U1") (pin "55") (pinfunction "VUSB_55") (pintype "bidirectional"))
      (node (ref "U1") (pin "62") (pinfunction "VDD5_62") (pintype "bidirectional"))
      (node (ref "U1") (pin "86") (pinfunction "ENVREG_86") (pintype "bidirectional"))
    )
    (net (code "58") (name "AC_HOT") (class "Default")
      (node (ref "B2") (pin "AC1") (pinfunction "AC1_AC1") (pintype "passive"))
      (node (ref "F2") (pin "2") (pinfunction "2_2") (pintype "passive"))
      (node (ref "R29") (pin "1") (pinfunction "1_1") (pintype "passive"))
      (node (ref "R34") (pin "1") (pinfunction "1_1") (pintype "passive"))
      (node (ref "R35") (pin "1") (pinfunction "1_1") (pintype "passive"))
      (node (ref "R36") (pin "1") (pinfunction "1_1") (pintype "passive"))
      (node (ref "R37") (pin "1") (pinfunction "1_1") (pintype "passive"))
      (node (ref "R38") (pin "1") (pinfunction "1_1") (pintype "passive"))
      (node (ref "R39") (pin "1") (pinfunction "1_1") (pintype "passive"))
      (node (ref "R40") (pin "1") (pinfunction "1_1") (pintype "passive"))
      (node (ref "R41") (pin "1") (pinfunction "1_1") (pintype "passive"))
      (node (ref "R42") (pin "1") (pinfunction "1_1") (pintype "passive"))
      (node (ref "R43") (pin "1") (pinfunction "1_1") (pintype "passive"))
      (node (ref "R44") (pin "1") (pinfunction "1_1") (pintype "passive"))
      (node (ref "T1") (pin "2") (pinfunction "A2_2") (pintype "passive"))
      (node (ref "T10") (pin "2") (pinfunction "A2_2") (pintype "passive"))
      (node (ref "T15") (pin "2") (pinfunction "A2_2") (pintype "passive"))
      (node (ref "T16") (pin "2") (pinfunction "A2_2") (pintype "passive"))
      (node (ref "T2") (pin "2") (pinfunction "A2_2") (pintype "passive"))
      (node (ref "T3") (pin "2") (pinfunction "A2_2") (pintype "passive"))
      (node (ref "T4") (pin "2") (pinfunction "A2_2") (pintype "passive"))
      (node (ref "T5") (pin "2") (pinfunction "A2_2") (pintype "passive"))
      (node (ref "T6") (pin "2") (pinfunction "A2_2") (pintype "passive"))
      (node (ref "T7") (pin "2") (pinfunction "A2_2") (pintype "passive"))
      (node (ref "T8") (pin "2") (pinfunction "A2_2") (pintype "passive"))
      (node (ref "T9") (pin "2") (pinfunction "A2_2") (pintype "passive"))
    )
    (net (code "59") (name "GND") (class "Default")
      (node (ref "B2") (pin "-") (pinfunction "-_-") (pintype "passive"))
      (node (ref "C10") (pin "C") (pinfunction "-_C") (pintype "passive"))
      (node (ref "C11") (pin "1") (pinfunction "1_1") (pintype "passive"))
      (node (ref "C12") (pin "1") (pinfunction "1_1") (pintype "passive"))
      (node (ref "C13") (pin "2") (pinfunction "2_2") (pintype "passive"))
      (node (ref "C14") (pin "2") (pinfunction "2_2") (pintype "passive"))
      (node (ref "C15") (pin "-") (pinfunction "-_-") (pintype "passive"))
      (node (ref "C16") (pin "2") (pinfunction "2_2") (pintype "passive"))
      (node (ref "C3") (pin "2") (pinfunction "2_2") (pintype "passive"))
      (node (ref "C4") (pin "2") (pinfunction "2_2") (pintype "passive"))
      (node (ref "C5") (pin "2") (pinfunction "2_2") (pintype "passive"))
      (node (ref "C6") (pin "2") (pinfunction "2_2") (pintype "passive"))
      (node (ref "C7") (pin "2") (pinfunction "2_2") (pintype "passive"))
      (node (ref "C9") (pin "2") (pinfunction "2_2") (pintype "passive"))
      (node (ref "JP1") (pin "3") (pinfunction "3_3") (pintype "passive"))
      (node (ref "OK1") (pin "2") (pinfunction "C_2") (pintype "passive"))
      (node (ref "OK10") (pin "2") (pinfunction "C_2") (pintype "passive"))
      (node (ref "OK15") (pin "2") (pinfunction "C_2") (pintype "passive"))
      (node (ref "OK16") (pin "2") (pinfunction "C_2") (pintype "passive"))
      (node (ref "OK2") (pin "2") (pinfunction "C_2") (pintype "passive"))
      (node (ref "OK3") (pin "2") (pinfunction "C_2") (pintype "passive"))
      (node (ref "OK4") (pin "2") (pinfunction "C_2") (pintype "passive"))
      (node (ref "OK5") (pin "2") (pinfunction "C_2") (pintype "passive"))
      (node (ref "OK6") (pin "2") (pinfunction "C_2") (pintype "passive"))
      (node (ref "OK7") (pin "2") (pinfunction "C_2") (pintype "passive"))
      (node (ref "OK8") (pin "2") (pinfunction "C_2") (pintype "passive"))
      (node (ref "OK9") (pin "2") (pinfunction "C_2") (pintype "passive"))
      (node (ref "PWR1") (pin "C") (pinfunction "C_C") (pintype "passive"))
      (node (ref "R6") (pin "1") (pinfunction "1_1") (pintype "passive"))
      (node (ref "S1") (pin "1") (pinfunction "1_1") (pintype "passive"))
      (node (ref "S1") (pin "2") (pinfunction "2_2") (pintype "passive"))
      (node (ref "S2") (pin "1") (pinfunction "1_1") (pintype "passive"))
      (node (ref "S2") (pin "2") (pinfunction "2_2") (pintype "passive"))
      (node (ref "U$1") (pin "1") (pinfunction "GND_1") (pintype "bidirectional"))
      (node (ref "U$1") (pin "10") (pinfunction "GND_10") (pintype "bidirectional"))
      (node (ref "U$1") (pin "18") (pinfunction "GND_18") (pintype "bidirectional"))
      (node (ref "U$1") (pin "19") (pinfunction "GND_19") (pintype "bidirectional"))
      (node (ref "U$1") (pin "25") (pinfunction "GND_25") (pintype "bidirectional"))
      (node (ref "U$1") (pin "28") (pinfunction "GND_28") (pintype "bidirectional"))
      (node (ref "U$1") (pin "30") (pinfunction "GND_30") (pintype "bidirectional"))
      (node (ref "U$1") (pin "36") (pinfunction "GND_36") (pintype "bidirectional"))
      (node (ref "U$2") (pin "12") (pinfunction "SHIELD_12") (pintype "bidirectional"))
      (node (ref "U$2") (pin "3") (pinfunction "GND_3") (pintype "bidirectional"))
      (node (ref "U$2") (pin "6") (pinfunction "GND1_6") (pintype "bidirectional"))
      (node (ref "U$2") (pin "VSS") (pinfunction "SW_VSS") (pintype "bidirectional"))
      (node (ref "U$21") (pin "GND") (pinfunction "GND_GND") (pintype "bidirectional"))
      (node (ref "U$21") (pin "MTN1") (pinfunction "MTN2_MTN1") (pintype "bidirectional"))
      (node (ref "U$21") (pin "MTN2") (pinfunction "MTN3_MTN2") (pintype "bidirectional"))
      (node (ref "U$21") (pin "MTN3") (pinfunction "MTN1_MTN3") (pintype "bidirectional"))
      (node (ref "U$21") (pin "MTN4") (pinfunction "MTN4_MTN4") (pintype "bidirectional"))
      (node (ref "U1") (pin "15") (pinfunction "VSS1_15") (pintype "bidirectional"))
      (node (ref "U1") (pin "31") (pinfunction "AVSS_31") (pintype "bidirectional"))
      (node (ref "U1") (pin "36") (pinfunction "VSS2_36") (pintype "bidirectional"))
      (node (ref "U1") (pin "45") (pinfunction "VSS3_45") (pintype "bidirectional"))
      (node (ref "U1") (pin "65") (pinfunction "VSS4_65") (pintype "bidirectional"))
      (node (ref "U1") (pin "75") (pinfunction "VSS6_75") (pintype "bidirectional"))
      (node (ref "U3") (pin "GND") (pinfunction "GND_GND") (pintype "input"))
    )
    (net (code "60") (name "Net-(C10-+)") (class "Default")
      (node (ref "C10") (pin "A") (pinfunction "+_A") (pintype "passive"))
      (node (ref "C9") (pin "1") (pinfunction "1_1") (pintype "passive"))
      (node (ref "U1") (pin "85") (pinfunction "VCAP/VDDCORE_85") (pintype "bidirectional"))
    )
    (net (code "61") (name "Net-(F2-Pad1)") (class "Default")
      (node (ref "F2") (pin "1") (pinfunction "1_1") (pintype "passive"))
      (node (ref "J2") (pin "PWR") (pinfunction "PWR_PWR") (pintype "bidirectional"))
    )
    (net (code "62") (name "Net-(LED1-PadA)") (class "Default")
      (node (ref "LED1") (pin "A") (pinfunction "A_A") (pintype "passive"))
      (node (ref "R14") (pin "1") (pinfunction "1_1") (pintype "passive"))
    )
    (net (code "63") (name "Net-(LED2-PadA)") (class "Default")
      (node (ref "LED2") (pin "A") (pinfunction "A_A") (pintype "passive"))
      (node (ref "R13") (pin "1") (pinfunction "1_1") (pintype "passive"))
    )
    (net (code "64") (name "Net-(LED3-PadA)") (class "Default")
      (node (ref "LED3") (pin "A") (pinfunction "A_A") (pintype "passive"))
      (node (ref "R12") (pin "1") (pinfunction "1_1") (pintype "passive"))
    )
    (net (code "65") (name "Net-(OK1-A)") (class "Default")
      (node (ref "OK1") (pin "1") (pinfunction "A_1") (pintype "passive"))
      (node (ref "R19") (pin "1") (pinfunction "1_1") (pintype "passive"))
    )
    (net (code "66") (name "Net-(OK1-A1)") (class "Default")
      (node (ref "OK1") (pin "4") (pinfunction "A1_4") (pintype "passive"))
      (node (ref "T1") (pin "3") (pinfunction "G_3") (pintype "passive"))
    )
    (net (code "67") (name "Net-(OK1-A2)") (class "Default")
      (node (ref "OK1") (pin "6") (pinfunction "A2_6") (pintype "passive"))
      (node (ref "R35") (pin "2") (pinfunction "2_2") (pintype "passive"))
    )
    (net (code "68") (name "Net-(OK2-A)") (class "Default")
      (node (ref "OK2") (pin "1") (pinfunction "A_1") (pintype "passive"))
      (node (ref "R18") (pin "1") (pinfunction "1_1") (pintype "passive"))
    )
    (net (code "69") (name "Net-(OK2-A1)") (class "Default")
      (node (ref "OK2") (pin "4") (pinfunction "A1_4") (pintype "passive"))
      (node (ref "T2") (pin "3") (pinfunction "G_3") (pintype "passive"))
    )
    (net (code "70") (name "Net-(OK2-A2)") (class "Default")
      (node (ref "OK2") (pin "6") (pinfunction "A2_6") (pintype "passive"))
      (node (ref "R34") (pin "2") (pinfunction "2_2") (pintype "passive"))
    )
    (net (code "71") (name "Net-(OK3-A)") (class "Default")
      (node (ref "OK3") (pin "1") (pinfunction "A_1") (pintype "passive"))
      (node (ref "R26") (pin "1") (pinfunction "1_1") (pintype "passive"))
    )
    (net (code "72") (name "Net-(OK3-A1)") (class "Default")
      (node (ref "OK3") (pin "4") (pinfunction "A1_4") (pintype "passive"))
      (node (ref "T3") (pin "3") (pinfunction "G_3") (pintype "passive"))
    )
    (net (code "73") (name "Net-(OK3-A2)") (class "Default")
      (node (ref "OK3") (pin "6") (pinfunction "A2_6") (pintype "passive"))
      (node (ref "R42") (pin "2") (pinfunction "2_2") (pintype "passive"))
    )
    (net (code "74") (name "Net-(OK4-A)") (class "Default")
      (node (ref "OK4") (pin "1") (pinfunction "A_1") (pintype "passive"))
      (node (ref "R27") (pin "1") (pinfunction "1_1") (pintype "passive"))
    )
    (net (code "75") (name "Net-(OK4-A1)") (class "Default")
      (node (ref "OK4") (pin "4") (pinfunction "A1_4") (pintype "passive"))
      (node (ref "T4") (pin "3") (pinfunction "G_3") (pintype "passive"))
    )
    (net (code "76") (name "Net-(OK4-A2)") (class "Default")
      (node (ref "OK4") (pin "6") (pinfunction "A2_6") (pintype "passive"))
      (node (ref "R43") (pin "2") (pinfunction "2_2") (pintype "passive"))
    )
    (net (code "77") (name "Net-(OK5-A)") (class "Default")
      (node (ref "OK5") (pin "1") (pinfunction "A_1") (pintype "passive"))
      (node (ref "R28") (pin "1") (pinfunction "1_1") (pintype "passive"))
    )
    (net (code "78") (name "Net-(OK5-A1)") (class "Default")
      (node (ref "OK5") (pin "4") (pinfunction "A1_4") (pintype "passive"))
      (node (ref "T5") (pin "3") (pinfunction "G_3") (pintype "passive"))
    )
    (net (code "79") (name "Net-(OK5-A2)") (class "Default")
      (node (ref "OK5") (pin "6") (pinfunction "A2_6") (pintype "passive"))
      (node (ref "R44") (pin "2") (pinfunction "2_2") (pintype "passive"))
    )
    (net (code "80") (name "Net-(OK6-A)") (class "Default")
      (node (ref "OK6") (pin "1") (pinfunction "A_1") (pintype "passive"))
      (node (ref "R30") (pin "1") (pinfunction "1_1") (pintype "passive"))
    )
    (net (code "81") (name "Net-(OK6-A1)") (class "Default")
      (node (ref "OK6") (pin "4") (pinfunction "A1_4") (pintype "passive"))
      (node (ref "T6") (pin "3") (pinfunction "G_3") (pintype "passive"))
    )
    (net (code "82") (name "Net-(OK6-A2)") (class "Default")
      (node (ref "OK6") (pin "6") (pinfunction "A2_6") (pintype "passive"))
      (node (ref "R29") (pin "2") (pinfunction "2_2") (pintype "passive"))
    )
    (net (code "83") (name "Net-(OK7-A)") (class "Default")
      (node (ref "OK7") (pin "1") (pinfunction "A_1") (pintype "passive"))
      (node (ref "R21") (pin "1") (pinfunction "1_1") (pintype "passive"))
    )
    (net (code "84") (name "Net-(OK7-A1)") (class "Default")
      (node (ref "OK7") (pin "4") (pinfunction "A1_4") (pintype "passive"))
      (node (ref "T7") (pin "3") (pinfunction "G_3") (pintype "passive"))
    )
    (net (code "85") (name "Net-(OK7-A2)") (class "Default")
      (node (ref "OK7") (pin "6") (pinfunction "A2_6") (pintype "passive"))
      (node (ref "R37") (pin "2") (pinfunction "2_2") (pintype "passive"))
    )
    (net (code "86") (name "Net-(OK8-A)") (class "Default")
      (node (ref "OK8") (pin "1") (pinfunction "A_1") (pintype "passive"))
      (node (ref "R20") (pin "1") (pinfunction "1_1") (pintype "passive"))
    )
    (net (code "87") (name "Net-(OK8-A1)") (class "Default")
      (node (ref "OK8") (pin "4") (pinfunction "A1_4") (pintype "passive"))
      (node (ref "T8") (pin "3") (pinfunction "G_3") (pintype "passive"))
    )
    (net (code "88") (name "Net-(OK8-A2)") (class "Default")
      (node (ref "OK8") (pin "6") (pinfunction "A2_6") (pintype "passive"))
      (node (ref "R36") (pin "2") (pinfunction "2_2") (pintype "passive"))
    )
    (net (code "89") (name "Net-(OK9-A)") (class "Default")
      (node (ref "OK9") (pin "1") (pinfunction "A_1") (pintype "passive"))
      (node (ref "R23") (pin "1") (pinfunction "1_1") (pintype "passive"))
    )
    (net (code "90") (name "Net-(OK9-A1)") (class "Default")
      (node (ref "OK9") (pin "4") (pinfunction "A1_4") (pintype "passive"))
      (node (ref "T9") (pin "3") (pinfunction "G_3") (pintype "passive"))
    )
    (net (code "91") (name "Net-(OK9-A2)") (class "Default")
      (node (ref "OK9") (pin "6") (pinfunction "A2_6") (pintype "passive"))
      (node (ref "R39") (pin "2") (pinfunction "2_2") (pintype "passive"))
    )
    (net (code "92") (name "Net-(OK10-A)") (class "Default")
      (node (ref "OK10") (pin "1") (pinfunction "A_1") (pintype "passive"))
      (node (ref "R22") (pin "1") (pinfunction "1_1") (pintype "passive"))
    )
    (net (code "93") (name "Net-(OK10-A1)") (class "Default")
      (node (ref "OK10") (pin "4") (pinfunction "A1_4") (pintype "passive"))
      (node (ref "T10") (pin "3") (pinfunction "G_3") (pintype "passive"))
    )
    (net (code "94") (name "Net-(OK10-A2)") (class "Default")
      (node (ref "OK10") (pin "6") (pinfunction "A2_6") (pintype "passive"))
      (node (ref "R38") (pin "2") (pinfunction "2_2") (pintype "passive"))
    )
    (net (code "95") (name "Net-(OK15-A)") (class "Default")
      (node (ref "OK15") (pin "1") (pinfunction "A_1") (pintype "passive"))
      (node (ref "R25") (pin "1") (pinfunction "1_1") (pintype "passive"))
    )
    (net (code "96") (name "Net-(OK15-A1)") (class "Default")
      (node (ref "OK15") (pin "4") (pinfunction "A1_4") (pintype "passive"))
      (node (ref "T15") (pin "3") (pinfunction "G_3") (pintype "passive"))
    )
    (net (code "97") (name "Net-(OK15-A2)") (class "Default")
      (node (ref "OK15") (pin "6") (pinfunction "A2_6") (pintype "passive"))
      (node (ref "R41") (pin "2") (pinfunction "2_2") (pintype "passive"))
    )
    (net (code "98") (name "Net-(OK16-A)") (class "Default")
      (node (ref "OK16") (pin "1") (pinfunction "A_1") (pintype "passive"))
      (node (ref "R24") (pin "1") (pinfunction "1_1") (pintype "passive"))
    )
    (net (code "99") (name "Net-(OK16-A1)") (class "Default")
      (node (ref "OK16") (pin "4") (pinfunction "A1_4") (pintype "passive"))
      (node (ref "T16") (pin "3") (pinfunction "G_3") (pintype "passive"))
    )
    (net (code "100") (name "Net-(OK16-A2)") (class "Default")
      (node (ref "OK16") (pin "6") (pinfunction "A2_6") (pintype "passive"))
      (node (ref "R40") (pin "2") (pinfunction "2_2") (pintype "passive"))
    )
    (net (code "101") (name "Net-(PWR1-PadA)") (class "Default")
      (node (ref "PWR1") (pin "A") (pinfunction "A_A") (pintype "passive"))
      (node (ref "R50") (pin "1") (pinfunction "1_1") (pintype "passive"))
    )
    (net (code "102") (name "Net-(R1-Pad1)") (class "Default")
      (node (ref "R1") (pin "1") (pinfunction "1_1") (pintype "passive"))
      (node (ref "R53") (pin "1") (pinfunction "1_1") (pintype "passive"))
    )
    (net (code "103") (name "Net-(R2-Pad2)") (class "Default")
      (node (ref "R2") (pin "2") (pinfunction "2_2") (pintype "passive"))
      (node (ref "R3") (pin "1") (pinfunction "1_1") (pintype "passive"))
    )
    (net (code "104") (name "Net-(R4-Pad2)") (class "Default")
      (node (ref "R4") (pin "2") (pinfunction "2_2") (pintype "passive"))
      (node (ref "R5") (pin "2") (pinfunction "2_2") (pintype "passive"))
    )
    (net (code "105") (name "Net-(R15-Pad1)") (class "Default")
      (node (ref "R15") (pin "1") (pinfunction "1_1") (pintype "passive"))
      (node (ref "USB") (pin "A") (pinfunction "A_A") (pintype "passive"))
    )
    (net (code "106") (name "Net-(R16-Pad1)") (class "Default")
      (node (ref "R16") (pin "1") (pinfunction "1_1") (pintype "passive"))
      (node (ref "R17") (pin "1") (pinfunction "1_1") (pintype "passive"))
    )
    (net (code "107") (name "Net-(R51-Pad1)") (class "Default")
      (node (ref "R51") (pin "1") (pinfunction "1_1") (pintype "passive"))
      (node (ref "R54") (pin "1") (pinfunction "1_1") (pintype "passive"))
    )
    (net (code "108") (name "Net-(U$1-JTAG_TCK)") (class "Default")
      (node (ref "R8") (pin "2") (pinfunction "2_2") (pintype "passive"))
      (node (ref "U$1") (pin "4") (pinfunction "JTAG_TCK_4") (pintype "bidirectional"))
    )
    (net (code "109") (name "Net-(U3-IN)") (class "Default")
      (node (ref "B2") (pin "+") (pinfunction "+_+") (pintype "passive"))
      (node (ref "C15") (pin "+") (pinfunction "+_+") (pintype "passive"))
      (node (ref "U3") (pin "VIN") (pinfunction "IN_VIN") (pintype "input"))
    )
    (net (code "110") (name "Net-(U3-OUT)") (class "Default")
      (node (ref "C16") (pin "1") (pinfunction "1_1") (pintype "passive"))
      (node (ref "F1") (pin "2") (pinfunction "2_2") (pintype "passive"))
      (node (ref "U3") (pin "VOUT") (pinfunction "OUT_VOUT") (pintype "output"))
    )
    (net (code "111") (name "unconnected-(U$1-DEBUG_RX-Pad26)") (class "Default")
      (node (ref "U$1") (pin "26") (pinfunction "DEBUG_RX_26") (pintype "bidirectional"))
    )
    (net (code "112") (name "unconnected-(U$1-DEBUG_TX-Pad27)") (class "Default")
      (node (ref "U$1") (pin "27") (pinfunction "DEBUG_TX_27") (pintype "bidirectional"))
    )
    (net (code "113") (name "unconnected-(U$1-JTAG_EN-Pad21)") (class "Default")
      (node (ref "U$1") (pin "21") (pinfunction "JTAG_EN_21") (pintype "bidirectional"))
    )
    (net (code "114") (name "unconnected-(U$1-JTAG_RST-Pad9)") (class "Default")
      (node (ref "U$1") (pin "9") (pinfunction "JTAG_RST_9") (pintype "bidirectional"))
    )
    (net (code "115") (name "unconnected-(U$1-JTAG_TDI-Pad6)") (class "Default")
      (node (ref "U$1") (pin "6") (pinfunction "JTAG_TDI_6") (pintype "bidirectional"))
    )
    (net (code "116") (name "unconnected-(U$1-JTAG_TDO-Pad3)") (class "Default")
      (node (ref "U$1") (pin "3") (pinfunction "JTAG_TDO_3") (pintype "bidirectional"))
    )
    (net (code "117") (name "unconnected-(U$1-JTAG_TMS-Pad5)") (class "Default")
      (node (ref "U$1") (pin "5") (pinfunction "JTAG_TMS_5") (pintype "bidirectional"))
    )
    (net (code "118") (name "unconnected-(U$1-NC-Pad2)") (class "Default")
      (node (ref "U$1") (pin "2") (pinfunction "NC_2") (pintype "bidirectional"))
    )
    (net (code "119") (name "unconnected-(U$1-NC-Pad8)") (class "Default")
      (node (ref "U$1") (pin "8") (pinfunction "NC_8") (pintype "bidirectional"))
    )
    (net (code "120") (name "unconnected-(U$1-NC-Pad11)") (class "Default")
      (node (ref "U$1") (pin "11") (pinfunction "NC_11") (pintype "bidirectional"))
    )
    (net (code "121") (name "unconnected-(U$1-NC-Pad12)") (class "Default")
      (node (ref "U$1") (pin "12") (pinfunction "NC_12") (pintype "bidirectional"))
    )
    (net (code "122") (name "unconnected-(U$1-NC-Pad13)") (class "Default")
      (node (ref "U$1") (pin "13") (pinfunction "NC_13") (pintype "bidirectional"))
    )
    (net (code "123") (name "unconnected-(U$1-NC-Pad14)") (class "Default")
      (node (ref "U$1") (pin "14") (pinfunction "NC_14") (pintype "bidirectional"))
    )
    (net (code "124") (name "unconnected-(U$1-NC-Pad15)") (class "Default")
      (node (ref "U$1") (pin "15") (pinfunction "NC_15") (pintype "bidirectional"))
    )
    (net (code "125") (name "unconnected-(U$1-NC-Pad22)") (class "Default")
      (node (ref "U$1") (pin "22") (pinfunction "NC_22") (pintype "bidirectional"))
    )
    (net (code "126") (name "unconnected-(U$1-NC-Pad24)") (class "Default")
      (node (ref "U$1") (pin "24") (pinfunction "NC_24") (pintype "bidirectional"))
    )
    (net (code "127") (name "unconnected-(U$1-NC-Pad31)") (class "Default")
      (node (ref "U$1") (pin "31") (pinfunction "NC_31") (pintype "bidirectional"))
    )
    (net (code "128") (name "unconnected-(U$2-IRQ-Pad8)") (class "Default")
      (node (ref "U$2") (pin "8") (pinfunction "IRQ_8") (pintype "bidirectional"))
    )
    (net (code "129") (name "unconnected-(U$2-P9-Pad9)") (class "Default")
      (node (ref "U$2") (pin "9") (pinfunction "P9_9") (pintype "bidirectional"))
    )
    (net (code "130") (name "unconnected-(U1-C1IN-{slash}AN4{slash}CN6{slash}RB4-Pad21)") (class "Default")
      (node (ref "U1") (pin "21") (pinfunction "C1IN-/AN4/CN6/RB4_21") (pintype "bidirectional"))
    )
    (net (code "131") (name "unconnected-(U1-C1OUT{slash}AN8{slash}RB8-Pad32)") (class "Default")
      (node (ref "U1") (pin "32") (pinfunction "C1OUT/AN8/RB8_32") (pintype "bidirectional"))
    )
    (net (code "132") (name "unconnected-(U1-C2IN+{slash}AN3{slash}CN5{slash}RB3-Pad22)") (class "Default")
      (node (ref "U1") (pin "22") (pinfunction "C2IN+/AN3/CN5/RB3_22") (pintype "bidirectional"))
    )
    (net (code "133") (name "unconnected-(U1-C2IN-{slash}AN2{slash}CN4{slash}RB2-Pad23)") (class "Default")
      (node (ref "U1") (pin "23") (pinfunction "C2IN-/AN2/CN4/RB2_23") (pintype "bidirectional"))
    )
    (net (code "134") (name "unconnected-(U1-C2OUT{slash}AN9{slash}RB9-Pad33)") (class "Default")
      (node (ref "U1") (pin "33") (pinfunction "C2OUT/AN9/RB9_33") (pintype "bidirectional"))
    )
    (net (code "135") (name "unconnected-(U1-CVREFOUT{slash}PMA13{slash}AN10{slash}RB10-Pad34)") (class "Default")
      (node (ref "U1") (pin "34") (pinfunction "CVREFOUT/PMA13/AN10/RB10_34") (pintype "bidirectional"))
    )
    (net (code "136") (name "unconnected-(U1-IC1{slash}RTCC{slash}RD8-Pad68)") (class "Default")
      (node (ref "U1") (pin "68") (pinfunction "IC1/RTCC/RD8_68") (pintype "bidirectional"))
    )
    (net (code "137") (name "unconnected-(U1-IC2{slash}SS1{slash}RD9-Pad69)") (class "Default")
      (node (ref "U1") (pin "69") (pinfunction "IC2/SS1/RD9_69") (pintype "bidirectional"))
    )
    (net (code "138") (name "unconnected-(U1-IC4{slash}PMCS1{slash}PMA14{slash}RD11-Pad71)") (class "Default")
      (node (ref "U1") (pin "71") (pinfunction "IC4/PMCS1/PMA14/RD11_71") (pintype "bidirectional"))
    )
    (net (code "139") (name "unconnected-(U1-INT2{slash}RE9-Pad19)") (class "Default")
      (node (ref "U1") (pin "19") (pinfunction "INT2/RE9_19") (pintype "bidirectional"))
    )
    (net (code "140") (name "unconnected-(U1-PGC1{slash}EMUC1{slash}AN1{slash}CN3{slash}RB1-Pad24)") (class "Default")
      (node (ref "U1") (pin "24") (pinfunction "PGC1/EMUC1/AN1/CN3/RB1_24") (pintype "bidirectional"))
    )
    (net (code "141") (name "unconnected-(U1-PGD1{slash}EMUD1{slash}AN0{slash}CN2{slash}RB0-Pad25)") (class "Default")
      (node (ref "U1") (pin "25") (pinfunction "PGD1/EMUD1/AN0/CN2/RB0_25") (pintype "bidirectional"))
    )
    (net (code "142") (name "unconnected-(U1-PMA2{slash}SS2{slash}CN11{slash}RG9-Pad14)") (class "Default")
      (node (ref "U1") (pin "14") (pinfunction "PMA2/SS2/CN11/RG9_14") (pintype "bidirectional"))
    )
    (net (code "143") (name "unconnected-(U1-PMA6{slash}VREF+{slash}CVREF+{slash}RA10-Pad29)") (class "Default")
      (node (ref "U1") (pin "29") (pinfunction "PMA6/VREF+/CVREF+/RA10_29") (pintype "bidirectional"))
    )
    (net (code "144") (name "unconnected-(U1-PMA7{slash}VREF-{slash}CVREF-{slash}RA9-Pad28)") (class "Default")
      (node (ref "U1") (pin "28") (pinfunction "PMA7/VREF-/CVREF-/RA9_28") (pintype "bidirectional"))
    )
    (net (code "145") (name "unconnected-(U1-PMA10{slash}AN13{slash}RB13-Pad42)") (class "Default")
      (node (ref "U1") (pin "42") (pinfunction "PMA10/AN13/RB13_42") (pintype "bidirectional"))
    )
    (net (code "146") (name "unconnected-(U1-PMA11{slash}AN12{slash}RB12-Pad41)") (class "Default")
      (node (ref "U1") (pin "41") (pinfunction "PMA11/AN12/RB12_41") (pintype "bidirectional"))
    )
    (net (code "147") (name "unconnected-(U1-PMA12{slash}AN11{slash}RB11-Pad35)") (class "Default")
      (node (ref "U1") (pin "35") (pinfunction "PMA12/AN11/RB11_35") (pintype "bidirectional"))
    )
    (net (code "148") (name "unconnected-(U1-PMALH{slash}PMA1{slash}AN14{slash}RB14-Pad43)") (class "Default")
      (node (ref "U1") (pin "43") (pinfunction "PMALH/PMA1/AN14/RB14_43") (pintype "bidirectional"))
    )
    (net (code "149") (name "unconnected-(U1-PMALL{slash}PMA0{slash}AN15{slash}OCFB{slash}CN12{slash}RB15-Pad44)") (class "Default")
      (node (ref "U1") (pin "44") (pinfunction "PMALL/PMA0/AN15/OCFB/CN12/RB15_44") (pintype "bidirectional"))
    )
    (net (code "150") (name "unconnected-(U1-PMD4{slash}RE4-Pad100)") (class "Default")
      (node (ref "U1") (pin "100") (pinfunction "PMD4/RE4_100") (pintype "bidirectional"))
    )
    (net (code "151") (name "unconnected-(U1-PMD5{slash}RE5-Pad3)") (class "Default")
      (node (ref "U1") (pin "3") (pinfunction "PMD5/RE5_3") (pintype "bidirectional"))
    )
    (net (code "152") (name "unconnected-(U1-PMD8{slash}RG0-Pad90)") (class "Default")
      (node (ref "U1") (pin "90") (pinfunction "PMD8/RG0_90") (pintype "bidirectional"))
    )
    (net (code "153") (name "unconnected-(U1-PMD9{slash}RG1-Pad89)") (class "Default")
      (node (ref "U1") (pin "89") (pinfunction "PMD9/RG1_89") (pintype "bidirectional"))
    )
    (net (code "154") (name "unconnected-(U1-PMD15{slash}CN16{slash}RD7-Pad84)") (class "Default")
      (node (ref "U1") (pin "84") (pinfunction "PMD15/CN16/RD7_84") (pintype "bidirectional"))
    )
    (net (code "155") (name "unconnected-(U1-RG15-Pad1)") (class "Default")
      (node (ref "U1") (pin "1") (pinfunction "RG15_1") (pintype "bidirectional"))
    )
    (net (code "156") (name "unconnected-(U1-SCL1{slash}INT3{slash}RA14-Pad66)") (class "Default")
      (node (ref "U1") (pin "66") (pinfunction "SCL1/INT3/RA14_66") (pintype "bidirectional"))
    )
    (net (code "157") (name "unconnected-(U1-SCL2{slash}RA2-Pad58)") (class "Default")
      (node (ref "U1") (pin "58") (pinfunction "SCL2/RA2_58") (pintype "bidirectional"))
    )
    (net (code "158") (name "unconnected-(U1-SDA1{slash}INT4{slash}RA15-Pad67)") (class "Default")
      (node (ref "U1") (pin "67") (pinfunction "SDA1/INT4/RA15_67") (pintype "bidirectional"))
    )
    (net (code "159") (name "unconnected-(U1-T2CK{slash}RC1-Pad6)") (class "Default")
      (node (ref "U1") (pin "6") (pinfunction "T2CK/RC1_6") (pintype "bidirectional"))
    )
    (net (code "160") (name "unconnected-(U1-T3CK{slash}RC2-Pad7)") (class "Default")
      (node (ref "U1") (pin "7") (pinfunction "T3CK/RC2_7") (pintype "bidirectional"))
    )
    (net (code "161") (name "unconnected-(U1-T4CK{slash}RC3-Pad8)") (class "Default")
      (node (ref "U1") (pin "8") (pinfunction "T4CK/RC3_8") (pintype "bidirectional"))
    )
    (net (code "162") (name "unconnected-(U1-TCK{slash}RA1-Pad38)") (class "Default")
      (node (ref "U1") (pin "38") (pinfunction "TCK/RA1_38") (pintype "bidirectional"))
    )
    (net (code "163") (name "unconnected-(U1-TDI{slash}RA4-Pad60)") (class "Default")
      (node (ref "U1") (pin "60") (pinfunction "TDI/RA4_60") (pintype "bidirectional"))
    )
    (net (code "164") (name "unconnected-(U1-TDO{slash}RA5-Pad61)") (class "Default")
      (node (ref "U1") (pin "61") (pinfunction "TDO/RA5_61") (pintype "bidirectional"))
    )
    (net (code "165") (name "unconnected-(U1-TMS{slash}RA0-Pad17)") (class "Default")
      (node (ref "U1") (pin "17") (pinfunction "TMS/RA0_17") (pintype "bidirectional"))
    )
    (net (code "166") (name "unconnected-(U1-TRCLK{slash}RA6-Pad91)") (class "Default")
      (node (ref "U1") (pin "91") (pinfunction "TRCLK/RA6_91") (pintype "bidirectional"))
    )
    (net (code "167") (name "unconnected-(U1-TRD3{slash}RA7-Pad92)") (class "Default")
      (node (ref "U1") (pin "92") (pinfunction "TRD3/RA7_92") (pintype "bidirectional"))
    )
    (net (code "168") (name "unconnected-(U1-U1RX{slash}RF2-Pad52)") (class "Default")
      (node (ref "U1") (pin "52") (pinfunction "U1RX/RF2_52") (pintype "bidirectional"))
    )
    (net (code "169") (name "unconnected-(U1-U1TX{slash}RF8-Pad53)") (class "Default")
      (node (ref "U1") (pin "53") (pinfunction "U1TX/RF8_53") (pintype "bidirectional"))
    )
    (net (code "170") (name "unconnected-(U1-U2CTS{slash}RF12-Pad40)") (class "Default")
      (node (ref "U1") (pin "40") (pinfunction "U2CTS/RF12_40") (pintype "bidirectional"))
    )
    (net (code "171") (name "unconnected-(U1-U2RTS{slash}BCLK2{slash}RF13-Pad39)") (class "Default")
      (node (ref "U1") (pin "39") (pinfunction "U2RTS/BCLK2/RF13_39") (pintype "bidirectional"))
    )
    (net (code "172") (name "unconnected-(U1-VBUSON{slash}C1IN+{slash}AN5{slash}CN7{slash}RB5-Pad20)") (class "Default")
      (node (ref "U1") (pin "20") (pinfunction "VBUSON/C1IN+/AN5/CN7/RB5_20") (pintype "bidirectional"))
    )
  )
)
